# Jacdaptor_FeatherWing-RevC.net
KiCad netlist of a schematic drawn in EAGLE
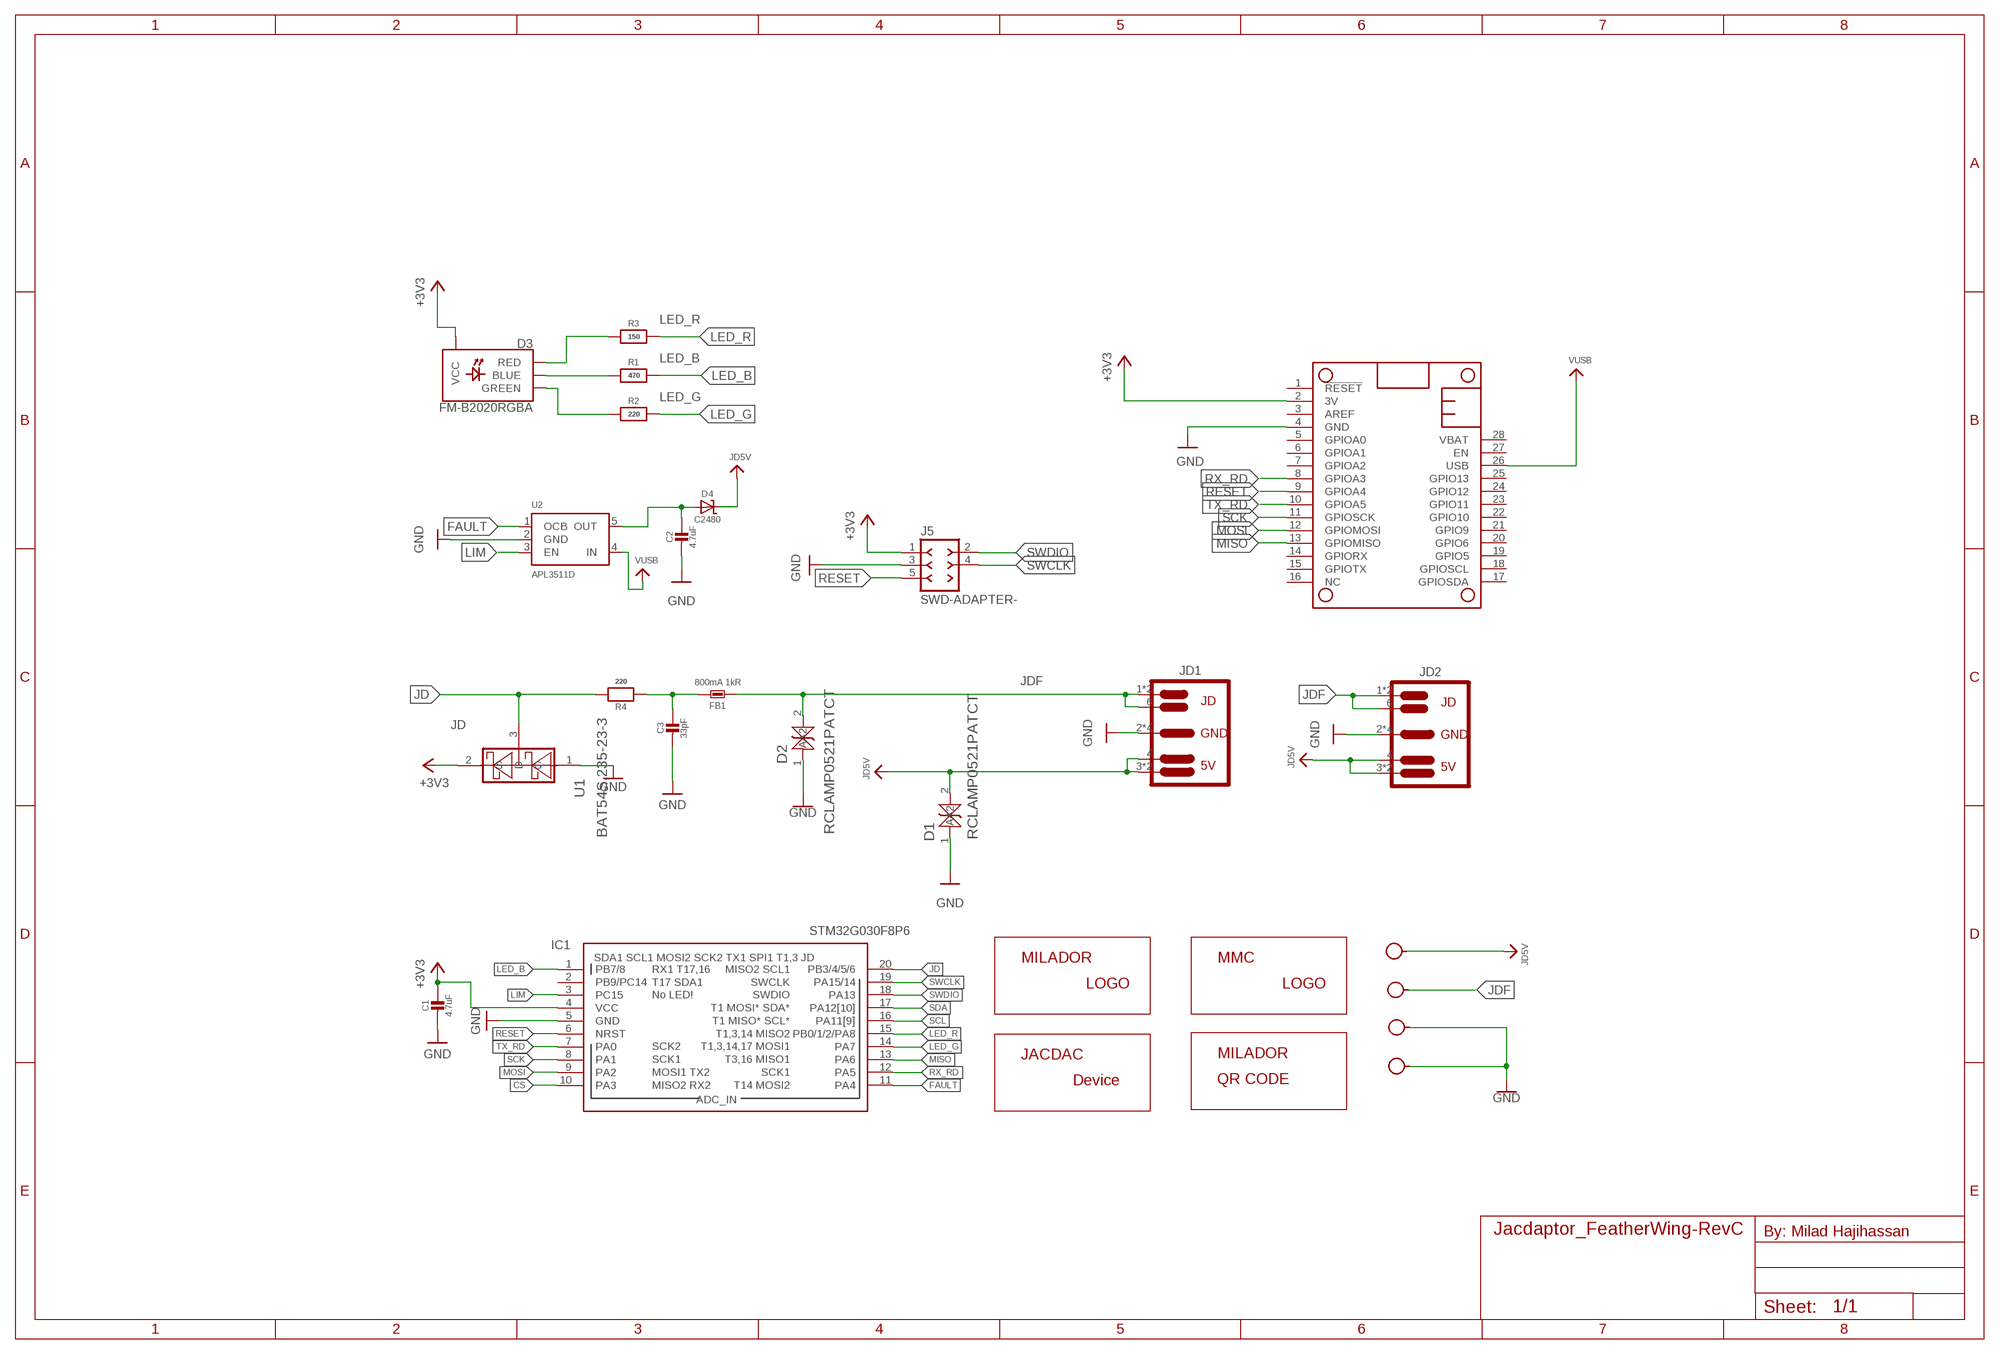
[diagram p0: schematic, sheet 1]

(export (version "E")
  (design (tool "Eeschema 10.0.6"))
  (components
    (comp (ref "C1")
      (value "4.7uF")
      (footprint "eagle-import:0603")
      (libsource (lib "eagle-import") (part "CAP_CERAMIC-0603"))
    )
    (comp (ref "C2")
      (value "4.7uF")
      (footprint "eagle-import:0603")
      (libsource (lib "eagle-import") (part "CAP_CERAMIC-0603"))
    )
    (comp (ref "C3")
      (value "33pF")
      (footprint "eagle-import:0603")
      (libsource (lib "eagle-import") (part "CAP_CERAMIC-0603"))
    )
    (comp (ref "D1")
      (value "RCLAMP0521PATCT")
      (footprint "eagle-import:DIODE-ZENER-0402")
      (fields (field (name "COPYRIGHT") "Copyright (C) 2021 Ultra Librarian. All rights reserved."))
      (libsource (lib "eagle-import") (part "DIODE-ZENER-AA-RCLAMP0521PATCT"))
    )
    (comp (ref "D2")
      (value "RCLAMP0521PATCT")
      (footprint "eagle-import:DIODE-ZENER-0402")
      (fields (field (name "COPYRIGHT") "Copyright (C) 2021 Ultra Librarian. All rights reserved."))
      (libsource (lib "eagle-import") (part "DIODE-ZENER-AA-RCLAMP0521PATCT"))
    )
    (comp (ref "D3")
      (value "FM-B2020RGBA")
      (footprint "eagle-import:LED-RGB-2121")
      (libsource (lib "eagle-import") (part "LED-RGB-2121-CA"))
    )
    (comp (ref "D4")
      (value "C2480")
      (footprint "eagle-import:DO214AC")
      (libsource (lib "eagle-import") (part "DIODE-SCHOTTKY-DO214AC"))
    )
    (comp (ref "FB1")
      (value "800mA 1kR")
      (footprint "eagle-import:0603-NO")
      (libsource (lib "eagle-import") (part "FERRITE-BEAD-0603-NO"))
    )
    (comp (ref "IC1")
      (value "STM32G030F8P6")
      (footprint "eagle-import:SOP65P640X120-20N")
      (libsource (lib "eagle-import") (part "STM32G030F8P6"))
    )
    (comp (ref "J1")
      (value "JACDAC-M3-DATA")
      (footprint "eagle-import:M3-HOLE-DATA")
      (libsource (lib "eagle-import") (part "JACDAC-M3-DATA"))
    )
    (comp (ref "J2")
      (value "JACDAC-M3-PWR")
      (footprint "eagle-import:M3-HOLE-PWR")
      (libsource (lib "eagle-import") (part "JACDAC-M3-PWR"))
    )
    (comp (ref "J3")
      (value "JACDAC-M3-GND")
      (footprint "eagle-import:M3-HOLE-GND")
      (libsource (lib "eagle-import") (part "JACDAC-M3-GND"))
    )
    (comp (ref "J4")
      (value "JACDAC-M3-GND")
      (footprint "eagle-import:M3-HOLE-GND")
      (libsource (lib "eagle-import") (part "JACDAC-M3-GND"))
    )
    (comp (ref "J5")
      (value "SWD-ADAPTER-")
      (footprint "eagle-import:SWD-ADAPTER")
      (libsource (lib "eagle-import") (part "SWD-ADAPTER-"))
    )
    (comp (ref "JD1")
      (value "JACDAC-EDGE-INNIE")
      (footprint "eagle-import:JD-EDGE-INNIE")
      (libsource (lib "eagle-import") (part "JACDAC-EDGE-INNIE"))
    )
    (comp (ref "JD2")
      (value "JACDAC-EDGE-INNIE")
      (footprint "eagle-import:JD-EDGE-INNIE")
      (libsource (lib "eagle-import") (part "JACDAC-EDGE-INNIE"))
    )
    (comp (ref "LABEL_DEVICE")
      (value "MILADOR-JACDAC-DEVICE-JACDAPTOR-WING")
      (footprint "eagle-import:JACDAPTOR-FEATHERWING")
      (libsource (lib "eagle-import") (part "MILADOR-JACDAC-DEVICE-JACDAPTOR-WING"))
    )
    (comp (ref "LABEL_LOGO")
      (value "MILADOR-LOGO-SM")
      (footprint "eagle-import:MILADOR_LOGO2")
      (libsource (lib "eagle-import") (part "MILADOR-LOGO-SM"))
    )
    (comp (ref "LABEL_MMC")
      (value "MMC_LOGO-XSM")
      (footprint "eagle-import:MMC_X-SMALL_LOGO")
      (libsource (lib "eagle-import") (part "MMC_LOGO-XSM"))
    )
    (comp (ref "LABEL_QR_CODE")
      (value "MILADOR-QR-CODE-JACDAC-FEATHERWING")
      (footprint "eagle-import:MILADOR_QR_JACDAC_FEATHERWING")
      (libsource (lib "eagle-import") (part "MILADOR-QR-CODE-JACDAC-FEATHERWING"))
    )
    (comp (ref "MS1")
      (value "ADAFRUIT_FEATHERWING_NODIM")
      (footprint "eagle-import:ADAFRUIT_FEATHERWING_DIM")
      (libsource (lib "eagle-import") (part "ADAFRUIT_FEATHERWING_NODIM"))
    )
    (comp (ref "R1")
      (value "470")
      (footprint "eagle-import:0603")
      (libsource (lib "eagle-import") (part "RESISTOR-0603"))
    )
    (comp (ref "R2")
      (value "220")
      (footprint "eagle-import:0603")
      (libsource (lib "eagle-import") (part "RESISTOR-0603"))
    )
    (comp (ref "R3")
      (value "150")
      (footprint "eagle-import:0603")
      (libsource (lib "eagle-import") (part "RESISTOR-0603"))
    )
    (comp (ref "R4")
      (value "220")
      (footprint "eagle-import:0603")
      (libsource (lib "eagle-import") (part "RESISTOR-0603"))
    )
    (comp (ref "U1")
      (value "BAT54S,235-23-3")
      (footprint "eagle-import:SOT23-3")
      (libsource (lib "eagle-import") (part "BAT54S,235-23-3"))
    )
    (comp (ref "U2")
      (value "APL3511D")
      (footprint "eagle-import:SOT23-5")
      (libsource (lib "eagle-import") (part "APL3511D"))
    )
  )
  (nets
    (net (code "1") (name "+3V3") (class "Default")
      (node (ref "C1") (pin "1") (pinfunction "1_1") (pintype "passive"))
      (node (ref "D3") (pin "PLUS") (pinfunction "VCC_PLUS") (pintype "bidirectional"))
      (node (ref "IC1") (pin "4") (pinfunction "VCC_4") (pintype "power_in"))
      (node (ref "J5") (pin "1") (pinfunction "VCC_1_1") (pintype "passive"))
      (node (ref "MS1") (pin "2") (pinfunction "3V_2") (pintype "power_in"))
      (node (ref "U1") (pin "2") (pinfunction "S_2") (pintype "passive"))
    )
    (net (code "2") (name "/VBAT") (class "Default")
      (node (ref "MS1") (pin "28") (pinfunction "VBAT_28") (pintype "power_in"))
    )
    (net (code "3") (name "CS") (class "Default")
      (node (ref "IC1") (pin "10") (pinfunction "PA3_10") (pintype "bidirectional"))
    )
    (net (code "4") (name "FAULT") (class "Default")
      (node (ref "IC1") (pin "11") (pinfunction "PA4_11") (pintype "bidirectional"))
      (node (ref "U2") (pin "1") (pinfunction "OCB_1") (pintype "bidirectional"))
    )
    (net (code "5") (name "GND") (class "Default")
      (node (ref "C1") (pin "2") (pinfunction "2_2") (pintype "passive"))
      (node (ref "C2") (pin "2") (pinfunction "2_2") (pintype "passive"))
      (node (ref "C3") (pin "2") (pinfunction "2_2") (pintype "passive"))
      (node (ref "D1") (pin "1") (pinfunction "A_1") (pintype "passive"))
      (node (ref "D2") (pin "1") (pinfunction "A_1") (pintype "passive"))
      (node (ref "IC1") (pin "5") (pinfunction "GND_5") (pintype "power_in"))
      (node (ref "J3") (pin "H") (pinfunction "P$1_H") (pintype "bidirectional"))
      (node (ref "J4") (pin "H") (pinfunction "P$1_H") (pintype "bidirectional"))
      (node (ref "J5") (pin "3") (pinfunction "GND_3_3") (pintype "passive"))
      (node (ref "JD1") (pin "2") (pinfunction "1_2") (pintype "power_in"))
      (node (ref "JD1") (pin "5") (pinfunction "1_5") (pintype "power_in"))
      (node (ref "JD1") (pin "P$2") (pinfunction "1_P$2") (pintype "power_in"))
      (node (ref "JD1") (pin "P$4") (pinfunction "1_P$4") (pintype "power_in"))
      (node (ref "JD2") (pin "2") (pinfunction "1_2") (pintype "power_in"))
      (node (ref "JD2") (pin "5") (pinfunction "1_5") (pintype "power_in"))
      (node (ref "JD2") (pin "P$2") (pinfunction "1_P$2") (pintype "power_in"))
      (node (ref "JD2") (pin "P$4") (pinfunction "1_P$4") (pintype "power_in"))
      (node (ref "MS1") (pin "4") (pinfunction "GND_4") (pintype "power_in"))
      (node (ref "U1") (pin "1") (pinfunction "G_1") (pintype "passive"))
      (node (ref "U2") (pin "2") (pinfunction "GND_2") (pintype "power_in"))
    )
    (net (code "6") (name "JD") (class "Default")
      (node (ref "IC1") (pin "20") (pinfunction "PB3/4/5/6_20") (pintype "bidirectional"))
      (node (ref "R4") (pin "2") (pinfunction "2_2") (pintype "passive"))
      (node (ref "U1") (pin "3") (pinfunction "D_3") (pintype "passive"))
    )
    (net (code "7") (name "JD5V") (class "Default")
      (node (ref "D1") (pin "2") (pinfunction "A2_2") (pintype "passive"))
      (node (ref "D4") (pin "C") (pinfunction "C_C") (pintype "passive"))
      (node (ref "J2") (pin "H") (pinfunction "P$1_H") (pintype "bidirectional"))
      (node (ref "JD1") (pin "3") (pinfunction "3_3") (pintype "power_in"))
      (node (ref "JD1") (pin "4") (pinfunction "4_4") (pintype "power_in"))
      (node (ref "JD1") (pin "P$1") (pinfunction "3_P$1") (pintype "power_in"))
      (node (ref "JD2") (pin "3") (pinfunction "3_3") (pintype "power_in"))
      (node (ref "JD2") (pin "4") (pinfunction "4_4") (pintype "power_in"))
      (node (ref "JD2") (pin "P$1") (pinfunction "3_P$1") (pintype "power_in"))
    )
    (net (code "8") (name "JDF") (class "Default")
      (node (ref "D2") (pin "2") (pinfunction "A2_2") (pintype "passive"))
      (node (ref "FB1") (pin "2") (pinfunction "2_2") (pintype "passive"))
      (node (ref "J1") (pin "H") (pinfunction "P$1_H") (pintype "bidirectional"))
      (node (ref "JD1") (pin "1") (pinfunction "2_1") (pintype "bidirectional"))
      (node (ref "JD1") (pin "6") (pinfunction "6_6") (pintype "bidirectional"))
      (node (ref "JD1") (pin "P$3") (pinfunction "2_P$3") (pintype "bidirectional"))
      (node (ref "JD2") (pin "1") (pinfunction "2_1") (pintype "bidirectional"))
      (node (ref "JD2") (pin "6") (pinfunction "6_6") (pintype "bidirectional"))
      (node (ref "JD2") (pin "P$3") (pinfunction "2_P$3") (pintype "bidirectional"))
    )
    (net (code "9") (name "LED_B") (class "Default")
      (node (ref "IC1") (pin "1") (pinfunction "PB7/8_1") (pintype "input"))
      (node (ref "R1") (pin "2") (pinfunction "2_2") (pintype "passive"))
    )
    (net (code "10") (name "LED_G") (class "Default")
      (node (ref "IC1") (pin "14") (pinfunction "PA7_14") (pintype "bidirectional"))
      (node (ref "R2") (pin "2") (pinfunction "2_2") (pintype "passive"))
    )
    (net (code "11") (name "LED_R") (class "Default")
      (node (ref "IC1") (pin "15") (pinfunction "PB0/1/2/PA8_15") (pintype "input"))
      (node (ref "R3") (pin "2") (pinfunction "2_2") (pintype "passive"))
    )
    (net (code "12") (name "LIM") (class "Default")
      (node (ref "IC1") (pin "3") (pinfunction "PC15_3") (pintype "bidirectional"))
      (node (ref "U2") (pin "3") (pinfunction "EN_3") (pintype "input"))
    )
    (net (code "13") (name "MISO") (class "Default")
      (node (ref "IC1") (pin "13") (pinfunction "PA6_13") (pintype "bidirectional"))
      (node (ref "MS1") (pin "13") (pinfunction "GPIOMISO_13") (pintype "bidirectional"))
    )
    (net (code "14") (name "MOSI") (class "Default")
      (node (ref "IC1") (pin "9") (pinfunction "PA2_9") (pintype "bidirectional"))
      (node (ref "MS1") (pin "12") (pinfunction "GPIOMOSI_12") (pintype "bidirectional"))
    )
    (net (code "15") (name "Net-(C3-Pad1)") (class "Default")
      (node (ref "C3") (pin "1") (pinfunction "1_1") (pintype "passive"))
      (node (ref "FB1") (pin "1") (pinfunction "1_1") (pintype "passive"))
      (node (ref "R4") (pin "1") (pinfunction "1_1") (pintype "passive"))
    )
    (net (code "16") (name "Net-(D3-BLUE)") (class "Default")
      (node (ref "D3") (pin "B-") (pinfunction "BLUE_B-") (pintype "bidirectional"))
      (node (ref "R1") (pin "1") (pinfunction "1_1") (pintype "passive"))
    )
    (net (code "17") (name "Net-(D3-GREEN)") (class "Default")
      (node (ref "D3") (pin "G-") (pinfunction "GREEN_G-") (pintype "bidirectional"))
      (node (ref "R2") (pin "1") (pinfunction "1_1") (pintype "passive"))
    )
    (net (code "18") (name "Net-(D3-RED)") (class "Default")
      (node (ref "D3") (pin "R-") (pinfunction "RED_R-") (pintype "bidirectional"))
      (node (ref "R3") (pin "1") (pinfunction "1_1") (pintype "passive"))
    )
    (net (code "19") (name "Net-(U2-OUT)") (class "Default")
      (node (ref "C2") (pin "1") (pinfunction "1_1") (pintype "passive"))
      (node (ref "D4") (pin "A") (pinfunction "A_A") (pintype "passive"))
      (node (ref "U2") (pin "5") (pinfunction "OUT_5") (pintype "power_in"))
    )
    (net (code "20") (name "RESET") (class "Default")
      (node (ref "IC1") (pin "6") (pinfunction "NRST_6") (pintype "bidirectional"))
      (node (ref "J5") (pin "5") (pinfunction "RESET_5_5") (pintype "passive"))
      (node (ref "MS1") (pin "9") (pinfunction "GPIOA4_9") (pintype "bidirectional"))
    )
    (net (code "21") (name "RX_RD") (class "Default")
      (node (ref "IC1") (pin "12") (pinfunction "PA5_12") (pintype "bidirectional"))
      (node (ref "MS1") (pin "8") (pinfunction "GPIOA3_8") (pintype "bidirectional"))
    )
    (net (code "22") (name "SCK") (class "Default")
      (node (ref "IC1") (pin "8") (pinfunction "PA1_8") (pintype "bidirectional"))
      (node (ref "MS1") (pin "11") (pinfunction "GPIOSCK_11") (pintype "bidirectional"))
    )
    (net (code "23") (name "SCL") (class "Default")
      (node (ref "IC1") (pin "16") (pinfunction "PA11[9]_16") (pintype "bidirectional"))
    )
    (net (code "24") (name "SDA") (class "Default")
      (node (ref "IC1") (pin "17") (pinfunction "PA12[10]_17") (pintype "bidirectional"))
    )
    (net (code "25") (name "SWCLK") (class "Default")
      (node (ref "IC1") (pin "19") (pinfunction "PA15/14_19") (pintype "bidirectional"))
      (node (ref "J5") (pin "4") (pinfunction "SWCLK_4_4") (pintype "passive"))
    )
    (net (code "26") (name "SWDIO") (class "Default")
      (node (ref "IC1") (pin "18") (pinfunction "PA13_18") (pintype "bidirectional"))
      (node (ref "J5") (pin "2") (pinfunction "SWDIO_2_2") (pintype "passive"))
    )
    (net (code "27") (name "TX_RD") (class "Default")
      (node (ref "IC1") (pin "7") (pinfunction "PA0_7") (pintype "bidirectional"))
      (node (ref "MS1") (pin "10") (pinfunction "GPIOA5_10") (pintype "bidirectional"))
    )
    (net (code "28") (name "VUSB") (class "Default")
      (node (ref "MS1") (pin "26") (pinfunction "USB_26") (pintype "power_in"))
      (node (ref "U2") (pin "4") (pinfunction "IN_4") (pintype "power_in"))
    )
    (net (code "29") (name "unconnected-(IC1-PB9{slash}PC14-Pad2)") (class "Default")
      (node (ref "IC1") (pin "2") (pinfunction "PB9/PC14_2") (pintype "bidirectional"))
    )
    (net (code "30") (name "unconnected-(MS1-AREF-Pad3)") (class "Default")
      (node (ref "MS1") (pin "3") (pinfunction "AREF_3") (pintype "passive"))
    )
    (net (code "31") (name "unconnected-(MS1-EN-Pad27)") (class "Default")
      (node (ref "MS1") (pin "27") (pinfunction "EN_27") (pintype "passive"))
    )
    (net (code "32") (name "unconnected-(MS1-GPIO5-Pad19)") (class "Default")
      (node (ref "MS1") (pin "19") (pinfunction "GPIO5_19") (pintype "bidirectional"))
    )
    (net (code "33") (name "unconnected-(MS1-GPIO6-Pad20)") (class "Default")
      (node (ref "MS1") (pin "20") (pinfunction "GPIO6_20") (pintype "bidirectional"))
    )
    (net (code "34") (name "unconnected-(MS1-GPIO9-Pad21)") (class "Default")
      (node (ref "MS1") (pin "21") (pinfunction "GPIO9_21") (pintype "bidirectional"))
    )
    (net (code "35") (name "unconnected-(MS1-GPIO10-Pad22)") (class "Default")
      (node (ref "MS1") (pin "22") (pinfunction "GPIO10_22") (pintype "bidirectional"))
    )
    (net (code "36") (name "unconnected-(MS1-GPIO11-Pad23)") (class "Default")
      (node (ref "MS1") (pin "23") (pinfunction "GPIO11_23") (pintype "bidirectional"))
    )
    (net (code "37") (name "unconnected-(MS1-GPIO12-Pad24)") (class "Default")
      (node (ref "MS1") (pin "24") (pinfunction "GPIO12_24") (pintype "bidirectional"))
    )
    (net (code "38") (name "unconnected-(MS1-GPIO13-Pad25)") (class "Default")
      (node (ref "MS1") (pin "25") (pinfunction "GPIO13_25") (pintype "bidirectional"))
    )
    (net (code "39") (name "unconnected-(MS1-GPIOA0-Pad5)") (class "Default")
      (node (ref "MS1") (pin "5") (pinfunction "GPIOA0_5") (pintype "bidirectional"))
    )
    (net (code "40") (name "unconnected-(MS1-GPIOA1-Pad6)") (class "Default")
      (node (ref "MS1") (pin "6") (pinfunction "GPIOA1_6") (pintype "bidirectional"))
    )
    (net (code "41") (name "unconnected-(MS1-GPIOA2-Pad7)") (class "Default")
      (node (ref "MS1") (pin "7") (pinfunction "GPIOA2_7") (pintype "bidirectional"))
    )
    (net (code "42") (name "unconnected-(MS1-GPIORX-Pad14)") (class "Default")
      (node (ref "MS1") (pin "14") (pinfunction "GPIORX_14") (pintype "bidirectional"))
    )
    (net (code "43") (name "unconnected-(MS1-GPIOSCL-Pad18)") (class "Default")
      (node (ref "MS1") (pin "18") (pinfunction "GPIOSCL_18") (pintype "bidirectional"))
    )
    (net (code "44") (name "unconnected-(MS1-GPIOSDA-Pad17)") (class "Default")
      (node (ref "MS1") (pin "17") (pinfunction "GPIOSDA_17") (pintype "bidirectional"))
    )
    (net (code "45") (name "unconnected-(MS1-GPIOTX-Pad15)") (class "Default")
      (node (ref "MS1") (pin "15") (pinfunction "GPIOTX_15") (pintype "bidirectional"))
    )
    (net (code "46") (name "unconnected-(MS1-NC-Pad16)") (class "Default")
      (node (ref "MS1") (pin "16") (pinfunction "NC_16") (pintype "passive"))
    )
    (net (code "47") (name "unconnected-(MS1-~{RESET}-Pad1)") (class "Default")
      (node (ref "MS1") (pin "1") (pinfunction "~{RESET}_1") (pintype "passive"))
    )
  )
)
